# CV060_AI.net
KiCad netlist of a schematic drawn in Altium Designer
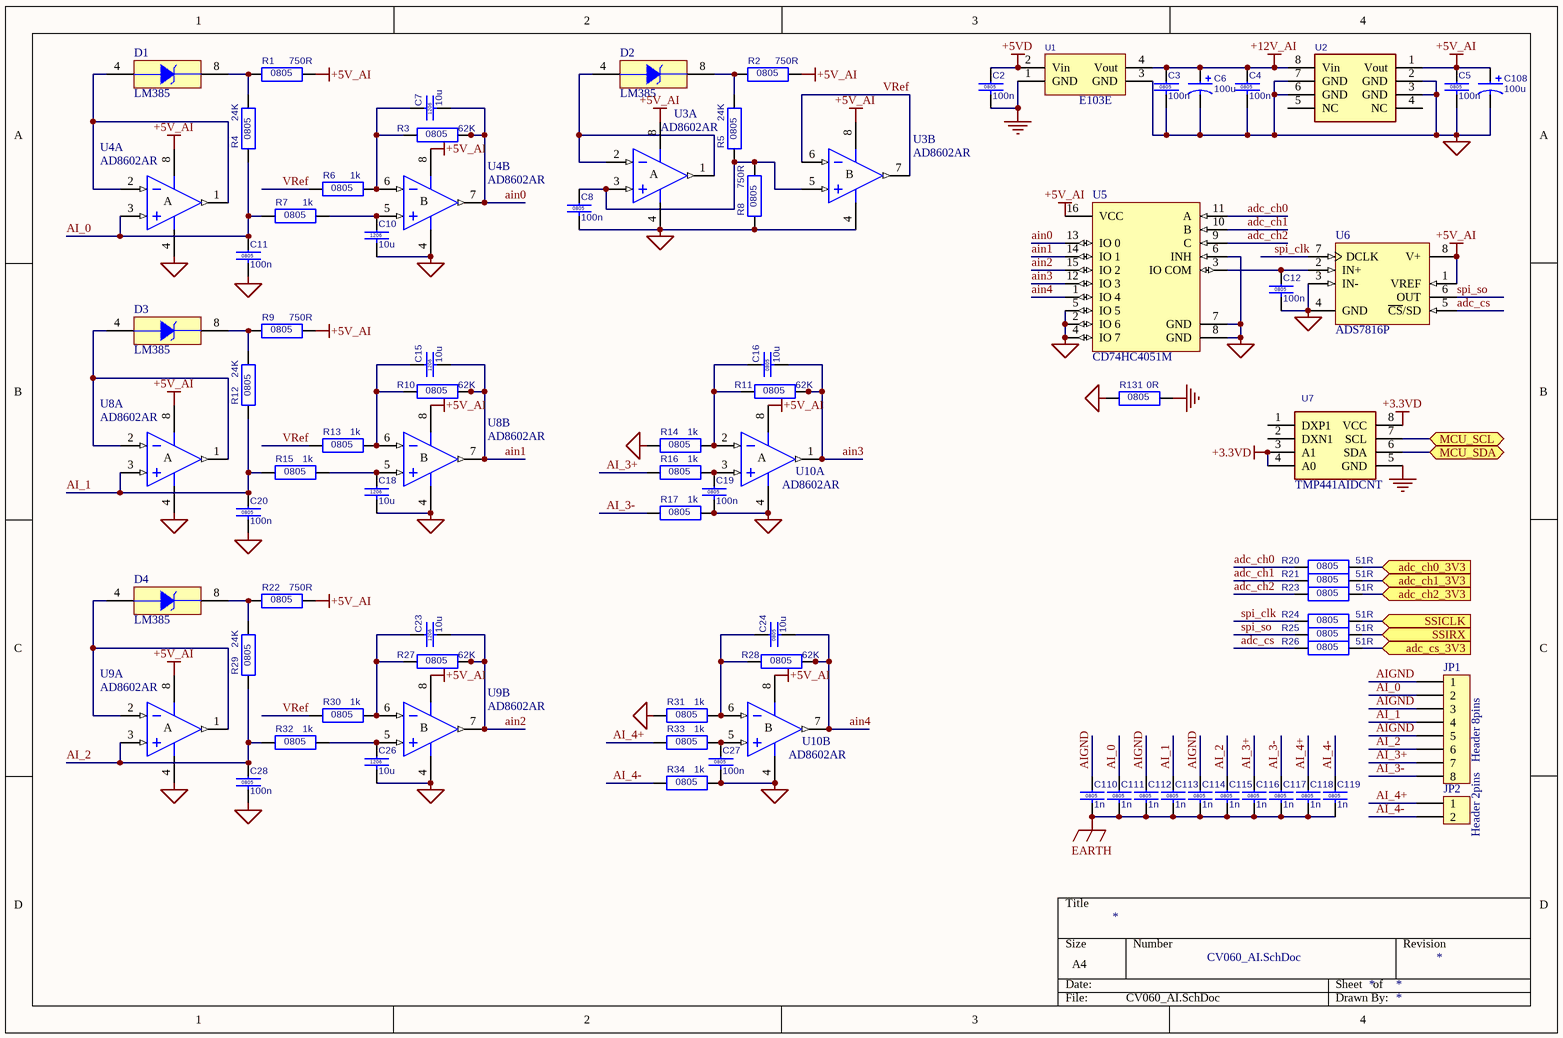
[diagram p0: CV060_AI.SchDoc]

(export (version "E")
  (design (tool "Eeschema 10.0.6"))
  (components
    (comp (ref "C2")
      (value "100n")
      (footprint "RC0805")
      (description "Chip capacitor, 20p")
      (fields
        (field (name "VOLTAGE") "50V")
        (field (name "MANUFACTURER") "KEMET, YAGEO")
        (field (name "CASE") "0805")
        (field (name "PUBLISHER") "ppavlov")
      )
      (libsource (lib "Aldiva_Altium_Library") (part "Capacitor_nonpolar_case"))
    )
    (comp (ref "C3")
      (value "100n")
      (footprint "RC0805")
      (description "Chip capacitor, 20p")
      (fields
        (field (name "VOLTAGE") "50V")
        (field (name "MANUFACTURER") "KEMET, YAGEO")
        (field (name "CASE") "0805")
        (field (name "PUBLISHER") "ppavlov")
      )
      (libsource (lib "Aldiva_Altium_Library") (part "Capacitor_nonpolar_case"))
    )
    (comp (ref "C4")
      (value "100n")
      (footprint "RC0805")
      (description "Chip capacitor, 20p")
      (fields
        (field (name "VOLTAGE") "50V")
        (field (name "MANUFACTURER") "KEMET, YAGEO")
        (field (name "CASE") "0805")
        (field (name "PUBLISHER") "ppavlov")
      )
      (libsource (lib "Aldiva_Altium_Library") (part "Capacitor_nonpolar_case"))
    )
    (comp (ref "C5")
      (value "100n")
      (footprint "RC0805")
      (description "Chip capacitor, 20p")
      (fields
        (field (name "VOLTAGE") "50V")
        (field (name "MANUFACTURER") "KEMET, YAGEO")
        (field (name "CASE") "0805")
        (field (name "PUBLISHER") "ppavlov")
      )
      (libsource (lib "Aldiva_Altium_Library") (part "Capacitor_nonpolar_case"))
    )
    (comp (ref "C6")
      (value "100u")
      (footprint "CEH12.5D5P2.5")
      (description "Electrolytic capacitor")
      (fields
        (field (name "PART NUMBER") "CEH12.5D5P2.5M-16V-100U")
        (field (name "VOLTAGE") "16V")
        (field (name "PUBLISHER") "ppavlov")
      )
      (libsource (lib "Aldiva_Altium_Library") (part "Capacitor_polar"))
    )
    (comp (ref "C7")
      (value "10u")
      (footprint "RC1206")
      (description "Chip capacitor, 20p")
      (fields
        (field (name "VOLTAGE") "10V")
        (field (name "MANUFACTURER") "AVX")
        (field (name "CASE") "1206")
        (field (name "PUBLISHER") "tkondratyuk")
      )
      (libsource (lib "Aldiva_Altium_Library") (part "Capacitor_nonpolar_case"))
    )
    (comp (ref "C8")
      (value "100n")
      (footprint "RC0805")
      (description "Chip capacitor, 20p")
      (fields
        (field (name "VOLTAGE") "50V")
        (field (name "MANUFACTURER") "KEMET, YAGEO")
        (field (name "CASE") "0805")
        (field (name "PUBLISHER") "ppavlov")
      )
      (libsource (lib "Aldiva_Altium_Library") (part "Capacitor_nonpolar_case"))
    )
    (comp (ref "C10")
      (value "10u")
      (footprint "RC1206")
      (description "Chip capacitor, 20p")
      (fields
        (field (name "VOLTAGE") "10V")
        (field (name "MANUFACTURER") "AVX")
        (field (name "CASE") "1206")
        (field (name "PUBLISHER") "tkondratyuk")
      )
      (libsource (lib "Aldiva_Altium_Library") (part "Capacitor_nonpolar_case"))
    )
    (comp (ref "C11")
      (value "100n")
      (footprint "RC0805")
      (description "Chip capacitor, 20p")
      (fields
        (field (name "VOLTAGE") "50V")
        (field (name "MANUFACTURER") "KEMET, YAGEO")
        (field (name "CASE") "0805")
        (field (name "PUBLISHER") "ppavlov")
      )
      (libsource (lib "Aldiva_Altium_Library") (part "Capacitor_nonpolar_case"))
    )
    (comp (ref "C12")
      (value "100n")
      (footprint "RC0805")
      (description "Chip capacitor, 20p")
      (fields
        (field (name "VOLTAGE") "50V")
        (field (name "MANUFACTURER") "KEMET, YAGEO")
        (field (name "CASE") "0805")
        (field (name "PUBLISHER") "ppavlov")
      )
      (libsource (lib "Aldiva_Altium_Library") (part "Capacitor_nonpolar_case"))
    )
    (comp (ref "C15")
      (value "10u")
      (footprint "RC1206")
      (description "Chip capacitor, 20p")
      (fields
        (field (name "VOLTAGE") "10V")
        (field (name "MANUFACTURER") "AVX")
        (field (name "CASE") "1206")
        (field (name "PUBLISHER") "tkondratyuk")
      )
      (libsource (lib "Aldiva_Altium_Library") (part "Capacitor_nonpolar_case"))
    )
    (comp (ref "C16")
      (value "10u")
      (footprint "RC0805")
      (description "Chip capacitor, 20p")
      (fields
        (field (name "VOLTAGE") "16V")
        (field (name "MANUFACTURER") "KEMET, YAGEO")
        (field (name "CASE") "0805")
        (field (name "PUBLISHER") "tkondratyuk")
      )
      (libsource (lib "Aldiva_Altium_Library") (part "Capacitor_nonpolar_case"))
    )
    (comp (ref "C18")
      (value "10u")
      (footprint "RC1206")
      (description "Chip capacitor, 20p")
      (fields
        (field (name "VOLTAGE") "10V")
        (field (name "MANUFACTURER") "AVX")
        (field (name "CASE") "1206")
        (field (name "PUBLISHER") "tkondratyuk")
      )
      (libsource (lib "Aldiva_Altium_Library") (part "Capacitor_nonpolar_case"))
    )
    (comp (ref "C19")
      (value "100n")
      (footprint "RC0805")
      (description "Chip capacitor, 20p")
      (fields
        (field (name "VOLTAGE") "50V")
        (field (name "MANUFACTURER") "KEMET, YAGEO")
        (field (name "CASE") "0805")
        (field (name "PUBLISHER") "ppavlov")
      )
      (libsource (lib "Aldiva_Altium_Library") (part "Capacitor_nonpolar_case"))
    )
    (comp (ref "C20")
      (value "100n")
      (footprint "RC0805")
      (description "Chip capacitor, 20p")
      (fields
        (field (name "VOLTAGE") "50V")
        (field (name "MANUFACTURER") "KEMET, YAGEO")
        (field (name "CASE") "0805")
        (field (name "PUBLISHER") "ppavlov")
      )
      (libsource (lib "Aldiva_Altium_Library") (part "Capacitor_nonpolar_case"))
    )
    (comp (ref "C23")
      (value "10u")
      (footprint "RC1206")
      (description "Chip capacitor, 20p")
      (fields
        (field (name "VOLTAGE") "10V")
        (field (name "MANUFACTURER") "AVX")
        (field (name "CASE") "1206")
        (field (name "PUBLISHER") "tkondratyuk")
      )
      (libsource (lib "Aldiva_Altium_Library") (part "Capacitor_nonpolar_case"))
    )
    (comp (ref "C24")
      (value "10u")
      (footprint "RC0805")
      (description "Chip capacitor, 20p")
      (fields
        (field (name "VOLTAGE") "16V")
        (field (name "MANUFACTURER") "KEMET, YAGEO")
        (field (name "CASE") "0805")
        (field (name "PUBLISHER") "tkondratyuk")
      )
      (libsource (lib "Aldiva_Altium_Library") (part "Capacitor_nonpolar_case"))
    )
    (comp (ref "C26")
      (value "10u")
      (footprint "RC1206")
      (description "Chip capacitor, 20p")
      (fields
        (field (name "VOLTAGE") "10V")
        (field (name "MANUFACTURER") "AVX")
        (field (name "CASE") "1206")
        (field (name "PUBLISHER") "tkondratyuk")
      )
      (libsource (lib "Aldiva_Altium_Library") (part "Capacitor_nonpolar_case"))
    )
    (comp (ref "C27")
      (value "100n")
      (footprint "RC0805")
      (description "Chip capacitor, 20p")
      (fields
        (field (name "VOLTAGE") "50V")
        (field (name "MANUFACTURER") "KEMET, YAGEO")
        (field (name "CASE") "0805")
        (field (name "PUBLISHER") "ppavlov")
      )
      (libsource (lib "Aldiva_Altium_Library") (part "Capacitor_nonpolar_case"))
    )
    (comp (ref "C28")
      (value "100n")
      (footprint "RC0805")
      (description "Chip capacitor, 20p")
      (fields
        (field (name "VOLTAGE") "50V")
        (field (name "MANUFACTURER") "KEMET, YAGEO")
        (field (name "CASE") "0805")
        (field (name "PUBLISHER") "ppavlov")
      )
      (libsource (lib "Aldiva_Altium_Library") (part "Capacitor_nonpolar_case"))
    )
    (comp (ref "C108")
      (value "100u")
      (footprint "CEH12.5D5P2.5")
      (description "Electrolytic capacitor")
      (fields
        (field (name "PART NUMBER") "CEH12.5D5P2.5M-16V-100U")
        (field (name "VOLTAGE") "16V")
        (field (name "PUBLISHER") "ppavlov")
      )
      (libsource (lib "Aldiva_Altium_Library") (part "Capacitor_polar"))
    )
    (comp (ref "C110")
      (value "1n")
      (footprint "RC0805")
      (description "Chip capacitor, 20p")
      (fields
        (field (name "VOLTAGE") "50V")
        (field (name "MANUFACTURER") "KEMET, YAGEO")
        (field (name "CASE") "0805")
        (field (name "PUBLISHER") "ppavlov")
      )
      (libsource (lib "Aldiva_Altium_Library") (part "Capacitor_nonpolar_case"))
    )
    (comp (ref "C111")
      (value "1n")
      (footprint "RC0805")
      (description "Chip capacitor, 20p")
      (fields
        (field (name "VOLTAGE") "50V")
        (field (name "MANUFACTURER") "KEMET, YAGEO")
        (field (name "CASE") "0805")
        (field (name "PUBLISHER") "ppavlov")
      )
      (libsource (lib "Aldiva_Altium_Library") (part "Capacitor_nonpolar_case"))
    )
    (comp (ref "C112")
      (value "1n")
      (footprint "RC0805")
      (description "Chip capacitor, 20p")
      (fields
        (field (name "VOLTAGE") "50V")
        (field (name "MANUFACTURER") "KEMET, YAGEO")
        (field (name "CASE") "0805")
        (field (name "PUBLISHER") "ppavlov")
      )
      (libsource (lib "Aldiva_Altium_Library") (part "Capacitor_nonpolar_case"))
    )
    (comp (ref "C113")
      (value "1n")
      (footprint "RC0805")
      (description "Chip capacitor, 20p")
      (fields
        (field (name "VOLTAGE") "50V")
        (field (name "MANUFACTURER") "KEMET, YAGEO")
        (field (name "CASE") "0805")
        (field (name "PUBLISHER") "ppavlov")
      )
      (libsource (lib "Aldiva_Altium_Library") (part "Capacitor_nonpolar_case"))
    )
    (comp (ref "C114")
      (value "1n")
      (footprint "RC0805")
      (description "Chip capacitor, 20p")
      (fields
        (field (name "VOLTAGE") "50V")
        (field (name "MANUFACTURER") "KEMET, YAGEO")
        (field (name "CASE") "0805")
        (field (name "PUBLISHER") "ppavlov")
      )
      (libsource (lib "Aldiva_Altium_Library") (part "Capacitor_nonpolar_case"))
    )
    (comp (ref "C115")
      (value "1n")
      (footprint "RC0805")
      (description "Chip capacitor, 20p")
      (fields
        (field (name "VOLTAGE") "50V")
        (field (name "MANUFACTURER") "KEMET, YAGEO")
        (field (name "CASE") "0805")
        (field (name "PUBLISHER") "ppavlov")
      )
      (libsource (lib "Aldiva_Altium_Library") (part "Capacitor_nonpolar_case"))
    )
    (comp (ref "C116")
      (value "1n")
      (footprint "RC0805")
      (description "Chip capacitor, 20p")
      (fields
        (field (name "VOLTAGE") "50V")
        (field (name "MANUFACTURER") "KEMET, YAGEO")
        (field (name "CASE") "0805")
        (field (name "PUBLISHER") "ppavlov")
      )
      (libsource (lib "Aldiva_Altium_Library") (part "Capacitor_nonpolar_case"))
    )
    (comp (ref "C117")
      (value "1n")
      (footprint "RC0805")
      (description "Chip capacitor, 20p")
      (fields
        (field (name "VOLTAGE") "50V")
        (field (name "MANUFACTURER") "KEMET, YAGEO")
        (field (name "CASE") "0805")
        (field (name "PUBLISHER") "ppavlov")
      )
      (libsource (lib "Aldiva_Altium_Library") (part "Capacitor_nonpolar_case"))
    )
    (comp (ref "C118")
      (value "1n")
      (footprint "RC0805")
      (description "Chip capacitor, 20p")
      (fields
        (field (name "VOLTAGE") "50V")
        (field (name "MANUFACTURER") "KEMET, YAGEO")
        (field (name "CASE") "0805")
        (field (name "PUBLISHER") "ppavlov")
      )
      (libsource (lib "Aldiva_Altium_Library") (part "Capacitor_nonpolar_case"))
    )
    (comp (ref "C119")
      (value "1n")
      (footprint "RC0805")
      (description "Chip capacitor, 20p")
      (fields
        (field (name "VOLTAGE") "50V")
        (field (name "MANUFACTURER") "KEMET, YAGEO")
        (field (name "CASE") "0805")
        (field (name "PUBLISHER") "ppavlov")
      )
      (libsource (lib "Aldiva_Altium_Library") (part "Capacitor_nonpolar_case"))
    )
    (comp (ref "D1")
      (value "LM385")
      (footprint "SO-8")
      (description "Micropower Voltage Reference Diode")
      (fields
        (field (name "PART NUMBER") "LM385BD-2-5")
        (field (name "MANUFACTURER") "TI")
        (field (name "PUBLISHER") "ppavlov")
      )
      (libsource (lib "Aldiva_Altium_Library") (part "LM385"))
    )
    (comp (ref "D2")
      (value "LM385")
      (footprint "SO-8")
      (description "Micropower Voltage Reference Diode")
      (fields
        (field (name "PART NUMBER") "LM385BD-2-5")
        (field (name "MANUFACTURER") "TI")
        (field (name "PUBLISHER") "ppavlov")
      )
      (libsource (lib "Aldiva_Altium_Library") (part "LM385"))
    )
    (comp (ref "D3")
      (value "LM385")
      (footprint "SO-8")
      (description "Micropower Voltage Reference Diode")
      (fields
        (field (name "PART NUMBER") "LM385BD-2-5")
        (field (name "MANUFACTURER") "TI")
        (field (name "PUBLISHER") "ppavlov")
      )
      (libsource (lib "Aldiva_Altium_Library") (part "LM385"))
    )
    (comp (ref "D4")
      (value "LM385")
      (footprint "SO-8")
      (description "Micropower Voltage Reference Diode")
      (fields
        (field (name "PART NUMBER") "LM385BD-2-5")
        (field (name "MANUFACTURER") "TI")
        (field (name "PUBLISHER") "ppavlov")
      )
      (libsource (lib "Aldiva_Altium_Library") (part "LM385"))
    )
    (comp (ref "JP1")
      (value "Header 8pins")
      (footprint "PHOENIX_5.08_8PINS")
      (description "5.08mm angled 8pins receptabe")
      (fields
        (field (name "PART NUMBER") "2EDGR-5.08-08P-14")
        (field (name "MANUFACTURER PART NUMBER") "2EDGR-5.0-08P-14")
        (field (name "PUBLISHER") "ppavlov")
      )
      (libsource (lib "Aldiva_Altium_Library") (part "Header 8pins"))
    )
    (comp (ref "JP2")
      (value "Header 2pins")
      (footprint "PHOENIX_5.08_2PINS")
      (description "5mm angled 2pins receptabe")
      (fields
        (field (name "PART NUMBER") "2EDGR-5.08-02P-14")
        (field (name "MANUFACTURER PART NUMBER") "2EDGR-5.0-02P-14")
        (field (name "PUBLISHER") "ppavlov")
      )
      (libsource (lib "Aldiva_Altium_Library") (part "Header 2pins"))
    )
    (comp (ref "R1")
      (value "750R")
      (footprint "RC0805")
      (description "Chip resistor")
      (fields
        (field (name "CASE") "0805")
        (field (name "PART NUMBER") "RC0805F-750R")
        (field (name "VOLTAGE") "200V")
        (field (name "PUBLISHER") "ppavlov")
      )
      (libsource (lib "Aldiva_Altium_Library") (part "Resistor"))
    )
    (comp (ref "R2")
      (value "750R")
      (footprint "RC0805")
      (description "Chip resistor")
      (fields
        (field (name "CASE") "0805")
        (field (name "PART NUMBER") "RC0805F-750R")
        (field (name "VOLTAGE") "200V")
        (field (name "PUBLISHER") "ppavlov")
      )
      (libsource (lib "Aldiva_Altium_Library") (part "Resistor"))
    )
    (comp (ref "R3")
      (value "62K")
      (footprint "RC0805")
      (description "Chip resistor")
      (fields
        (field (name "CASE") "0805")
        (field (name "PART NUMBER") "RC0805F-62K0")
        (field (name "VOLTAGE") "200V")
        (field (name "PUBLISHER") "ppavlov")
      )
      (libsource (lib "Aldiva_Altium_Library") (part "Resistor"))
    )
    (comp (ref "R4")
      (value "24K")
      (footprint "RC0805")
      (description "Chip resistor")
      (fields
        (field (name "CASE") "0805")
        (field (name "PART NUMBER") "RC0805F-24K0")
        (field (name "VOLTAGE") "200V")
        (field (name "PUBLISHER") "ppavlov")
      )
      (libsource (lib "Aldiva_Altium_Library") (part "Resistor"))
    )
    (comp (ref "R5")
      (value "24K")
      (footprint "RC0805")
      (description "Chip resistor")
      (fields
        (field (name "CASE") "0805")
        (field (name "PART NUMBER") "RC0805F-24K0")
        (field (name "VOLTAGE") "200V")
        (field (name "PUBLISHER") "ppavlov")
      )
      (libsource (lib "Aldiva_Altium_Library") (part "Resistor"))
    )
    (comp (ref "R6")
      (value "1k")
      (footprint "RC0805")
      (description "Chip resistor")
      (fields
        (field (name "CASE") "0805")
        (field (name "PART NUMBER") "RC0805F-1K00")
        (field (name "VOLTAGE") "200V")
        (field (name "PUBLISHER") "ppavlov")
      )
      (libsource (lib "Aldiva_Altium_Library") (part "Resistor"))
    )
    (comp (ref "R7")
      (value "1k")
      (footprint "RC0805")
      (description "Chip resistor")
      (fields
        (field (name "CASE") "0805")
        (field (name "PART NUMBER") "RC0805F-1K00")
        (field (name "VOLTAGE") "200V")
        (field (name "PUBLISHER") "ppavlov")
      )
      (libsource (lib "Aldiva_Altium_Library") (part "Resistor"))
    )
    (comp (ref "R8")
      (value "750R")
      (footprint "RC0805")
      (description "Chip resistor")
      (fields
        (field (name "CASE") "0805")
        (field (name "PART NUMBER") "RC0805F-750R")
        (field (name "VOLTAGE") "200V")
        (field (name "PUBLISHER") "ppavlov")
      )
      (libsource (lib "Aldiva_Altium_Library") (part "Resistor"))
    )
    (comp (ref "R9")
      (value "750R")
      (footprint "RC0805")
      (description "Chip resistor")
      (fields
        (field (name "CASE") "0805")
        (field (name "PART NUMBER") "RC0805F-750R")
        (field (name "VOLTAGE") "200V")
        (field (name "PUBLISHER") "ppavlov")
      )
      (libsource (lib "Aldiva_Altium_Library") (part "Resistor"))
    )
    (comp (ref "R10")
      (value "62K")
      (footprint "RC0805")
      (description "Chip resistor")
      (fields
        (field (name "CASE") "0805")
        (field (name "PART NUMBER") "RC0805F-62K0")
        (field (name "VOLTAGE") "200V")
        (field (name "PUBLISHER") "ppavlov")
      )
      (libsource (lib "Aldiva_Altium_Library") (part "Resistor"))
    )
    (comp (ref "R11")
      (value "62K")
      (footprint "RC0805")
      (description "Chip resistor")
      (fields
        (field (name "CASE") "0805")
        (field (name "PART NUMBER") "RC0805F-62K0")
        (field (name "VOLTAGE") "200V")
        (field (name "PUBLISHER") "ppavlov")
      )
      (libsource (lib "Aldiva_Altium_Library") (part "Resistor"))
    )
    (comp (ref "R12")
      (value "24K")
      (footprint "RC0805")
      (description "Chip resistor")
      (fields
        (field (name "CASE") "0805")
        (field (name "PART NUMBER") "RC0805F-24K0")
        (field (name "VOLTAGE") "200V")
        (field (name "PUBLISHER") "ppavlov")
      )
      (libsource (lib "Aldiva_Altium_Library") (part "Resistor"))
    )
    (comp (ref "R13")
      (value "1k")
      (footprint "RC0805")
      (description "Chip resistor")
      (fields
        (field (name "CASE") "0805")
        (field (name "PART NUMBER") "RC0805F-1K00")
        (field (name "VOLTAGE") "200V")
        (field (name "PUBLISHER") "ppavlov")
      )
      (libsource (lib "Aldiva_Altium_Library") (part "Resistor"))
    )
    (comp (ref "R14")
      (value "1k")
      (footprint "RC0805")
      (description "Chip resistor")
      (fields
        (field (name "CASE") "0805")
        (field (name "PART NUMBER") "RC0805F-1K00")
        (field (name "VOLTAGE") "200V")
        (field (name "PUBLISHER") "ppavlov")
      )
      (libsource (lib "Aldiva_Altium_Library") (part "Resistor"))
    )
    (comp (ref "R15")
      (value "1k")
      (footprint "RC0805")
      (description "Chip resistor")
      (fields
        (field (name "CASE") "0805")
        (field (name "PART NUMBER") "RC0805F-1K00")
        (field (name "VOLTAGE") "200V")
        (field (name "PUBLISHER") "ppavlov")
      )
      (libsource (lib "Aldiva_Altium_Library") (part "Resistor"))
    )
    (comp (ref "R16")
      (value "1k")
      (footprint "RC0805")
      (description "Chip resistor")
      (fields
        (field (name "CASE") "0805")
        (field (name "PART NUMBER") "RC0805F-1K00")
        (field (name "VOLTAGE") "200V")
        (field (name "PUBLISHER") "ppavlov")
      )
      (libsource (lib "Aldiva_Altium_Library") (part "Resistor"))
    )
    (comp (ref "R17")
      (value "1k")
      (footprint "RC0805")
      (description "Chip resistor")
      (fields
        (field (name "CASE") "0805")
        (field (name "PART NUMBER") "RC0805F-1K00")
        (field (name "VOLTAGE") "200V")
        (field (name "PUBLISHER") "ppavlov")
      )
      (libsource (lib "Aldiva_Altium_Library") (part "Resistor"))
    )
    (comp (ref "R20")
      (value "51R")
      (footprint "RC0805")
      (description "Chip resistor")
      (fields
        (field (name "CASE") "0805")
        (field (name "PART NUMBER") "RC0805F-51R0")
        (field (name "VOLTAGE") "200V")
        (field (name "PUBLISHER") "ppavlov")
      )
      (libsource (lib "Aldiva_Altium_Library") (part "Resistor"))
    )
    (comp (ref "R21")
      (value "51R")
      (footprint "RC0805")
      (description "Chip resistor")
      (fields
        (field (name "CASE") "0805")
        (field (name "PART NUMBER") "RC0805F-51R0")
        (field (name "VOLTAGE") "200V")
        (field (name "PUBLISHER") "ppavlov")
      )
      (libsource (lib "Aldiva_Altium_Library") (part "Resistor"))
    )
    (comp (ref "R22")
      (value "750R")
      (footprint "RC0805")
      (description "Chip resistor")
      (fields
        (field (name "CASE") "0805")
        (field (name "PART NUMBER") "RC0805F-750R")
        (field (name "VOLTAGE") "200V")
        (field (name "PUBLISHER") "ppavlov")
      )
      (libsource (lib "Aldiva_Altium_Library") (part "Resistor"))
    )
    (comp (ref "R23")
      (value "51R")
      (footprint "RC0805")
      (description "Chip resistor")
      (fields
        (field (name "CASE") "0805")
        (field (name "PART NUMBER") "RC0805F-51R0")
        (field (name "VOLTAGE") "200V")
        (field (name "PUBLISHER") "ppavlov")
      )
      (libsource (lib "Aldiva_Altium_Library") (part "Resistor"))
    )
    (comp (ref "R24")
      (value "51R")
      (footprint "RC0805")
      (description "Chip resistor")
      (fields
        (field (name "CASE") "0805")
        (field (name "PART NUMBER") "RC0805F-51R0")
        (field (name "VOLTAGE") "200V")
        (field (name "PUBLISHER") "ppavlov")
      )
      (libsource (lib "Aldiva_Altium_Library") (part "Resistor"))
    )
    (comp (ref "R25")
      (value "51R")
      (footprint "RC0805")
      (description "Chip resistor")
      (fields
        (field (name "CASE") "0805")
        (field (name "PART NUMBER") "RC0805F-51R0")
        (field (name "VOLTAGE") "200V")
        (field (name "PUBLISHER") "ppavlov")
      )
      (libsource (lib "Aldiva_Altium_Library") (part "Resistor"))
    )
    (comp (ref "R26")
      (value "51R")
      (footprint "RC0805")
      (description "Chip resistor")
      (fields
        (field (name "CASE") "0805")
        (field (name "PART NUMBER") "RC0805F-51R0")
        (field (name "VOLTAGE") "200V")
        (field (name "PUBLISHER") "ppavlov")
      )
      (libsource (lib "Aldiva_Altium_Library") (part "Resistor"))
    )
    (comp (ref "R27")
      (value "62K")
      (footprint "RC0805")
      (description "Chip resistor")
      (fields
        (field (name "CASE") "0805")
        (field (name "PART NUMBER") "RC0805F-62K0")
        (field (name "VOLTAGE") "200V")
        (field (name "PUBLISHER") "ppavlov")
      )
      (libsource (lib "Aldiva_Altium_Library") (part "Resistor"))
    )
    (comp (ref "R28")
      (value "62K")
      (footprint "RC0805")
      (description "Chip resistor")
      (fields
        (field (name "CASE") "0805")
        (field (name "PART NUMBER") "RC0805F-62K0")
        (field (name "VOLTAGE") "200V")
        (field (name "PUBLISHER") "ppavlov")
      )
      (libsource (lib "Aldiva_Altium_Library") (part "Resistor"))
    )
    (comp (ref "R29")
      (value "24K")
      (footprint "RC0805")
      (description "Chip resistor")
      (fields
        (field (name "CASE") "0805")
        (field (name "PART NUMBER") "RC0805F-24K0")
        (field (name "VOLTAGE") "200V")
        (field (name "PUBLISHER") "ppavlov")
      )
      (libsource (lib "Aldiva_Altium_Library") (part "Resistor"))
    )
    (comp (ref "R30")
      (value "1k")
      (footprint "RC0805")
      (description "Chip resistor")
      (fields
        (field (name "CASE") "0805")
        (field (name "PART NUMBER") "RC0805F-1K00")
        (field (name "VOLTAGE") "200V")
        (field (name "PUBLISHER") "ppavlov")
      )
      (libsource (lib "Aldiva_Altium_Library") (part "Resistor"))
    )
    (comp (ref "R31")
      (value "1k")
      (footprint "RC0805")
      (description "Chip resistor")
      (fields
        (field (name "CASE") "0805")
        (field (name "PART NUMBER") "RC0805F-1K00")
        (field (name "VOLTAGE") "200V")
        (field (name "PUBLISHER") "ppavlov")
      )
      (libsource (lib "Aldiva_Altium_Library") (part "Resistor"))
    )
    (comp (ref "R32")
      (value "1k")
      (footprint "RC0805")
      (description "Chip resistor")
      (fields
        (field (name "CASE") "0805")
        (field (name "PART NUMBER") "RC0805F-1K00")
        (field (name "VOLTAGE") "200V")
        (field (name "PUBLISHER") "ppavlov")
      )
      (libsource (lib "Aldiva_Altium_Library") (part "Resistor"))
    )
    (comp (ref "R33")
      (value "1k")
      (footprint "RC0805")
      (description "Chip resistor")
      (fields
        (field (name "CASE") "0805")
        (field (name "PART NUMBER") "RC0805F-1K00")
        (field (name "VOLTAGE") "200V")
        (field (name "PUBLISHER") "ppavlov")
      )
      (libsource (lib "Aldiva_Altium_Library") (part "Resistor"))
    )
    (comp (ref "R34")
      (value "1k")
      (footprint "RC0805")
      (description "Chip resistor")
      (fields
        (field (name "CASE") "0805")
        (field (name "PART NUMBER") "RC0805F-1K00")
        (field (name "VOLTAGE") "200V")
        (field (name "PUBLISHER") "ppavlov")
      )
      (libsource (lib "Aldiva_Altium_Library") (part "Resistor"))
    )
    (comp (ref "R131")
      (value "0R")
      (footprint "RC0805")
      (description "Chip resistor")
      (fields
        (field (name "CASE") "0805")
        (field (name "PART NUMBER") "RC0805F-000R")
        (field (name "VOLTAGE") "200V")
        (field (name "PUBLISHER") "ppavlov")
      )
      (libsource (lib "Aldiva_Altium_Library") (part "Resistor"))
    )
    (comp (ref "U1")
      (value "~")
      (footprint "SIP4")
      (description "1W Insulated DCDC converter 5 to 12V")
      (fields
        (field (name "PART NUMBER") "1-05-12S")
        (field (name "MANUFACTURER") "TI")
        (field (name "MANUFACTURER PART NUMBER") "E103E")
        (field (name "PUBLISHER") "ppavlov")
      )
      (libsource (lib "Aldiva_Altium_Library") (part "DCDC"))
    )
    (comp (ref "U2")
      (value "L78L05CD")
      (footprint "SO-8")
      (description "Regulator 100ma 5V")
      (fields (field (name "MANUFACTURER") "ST") (field (name "PUBLISHER") "ppavlov"))
      (libsource (lib "Aldiva_Altium_Library") (part "78L05"))
    )
    (comp (ref "U3")
      (value "AD8602AR")
      (footprint "SO-8")
      (description "Dual Precision, Low-Power BiFET Operational Amplifier")
      (fields (field (name "MANUFACTURER") "AD") (field (name "PUBLISHER") "ppavlov"))
      (libsource (lib "Aldiva_Altium_Library") (part "AD8602AR"))
    )
    (comp (ref "U4")
      (value "AD8602AR")
      (footprint "SO-8")
      (description "Dual Precision, Low-Power BiFET Operational Amplifier")
      (fields (field (name "MANUFACTURER") "AD") (field (name "PUBLISHER") "ppavlov"))
      (libsource (lib "Aldiva_Altium_Library") (part "AD8602AR"))
    )
    (comp (ref "U5")
      (value "CD74HC4051M")
      (footprint "SO-16")
      (description "High-Speed CMOS Logic\r\nAnalog Multiplexers/Demultiplexers")
      (fields (field (name "MANUFACTURER") "TI") (field (name "PUBLISHER") "ppavlov"))
      (libsource (lib "Aldiva_Altium_Library") (part "CD74HC4051M"))
    )
    (comp (ref "U6")
      (value "ADS7816P")
      (footprint "DIP-8")
      (description "12bit ADC")
      (fields (field (name "MANUFACTURER") "TI") (field (name "PUBLISHER") "ppavlov"))
      (libsource (lib "Aldiva_Altium_Library") (part "ADS7816P"))
    )
    (comp (ref "U7")
      (value "TMP441AIDCNT")
      (footprint "SOT23-8")
      (description "± 1 ° C TEMPERATURE SENSOR\r\nwith Automatic Beta Compensation")
      (fields (field (name "MANUFACTURER") "TI") (field (name "PUBLISHER") "ppavlov"))
      (libsource (lib "Aldiva_Altium_Library") (part "TMP441"))
    )
    (comp (ref "U8")
      (value "AD8602AR")
      (footprint "SO-8")
      (description "Dual Precision, Low-Power BiFET Operational Amplifier")
      (fields (field (name "MANUFACTURER") "AD") (field (name "PUBLISHER") "ppavlov"))
      (libsource (lib "Aldiva_Altium_Library") (part "AD8602AR"))
    )
    (comp (ref "U9")
      (value "AD8602AR")
      (footprint "SO-8")
      (description "Dual Precision, Low-Power BiFET Operational Amplifier")
      (fields (field (name "MANUFACTURER") "AD") (field (name "PUBLISHER") "ppavlov"))
      (libsource (lib "Aldiva_Altium_Library") (part "AD8602AR"))
    )
    (comp (ref "U10")
      (value "AD8602AR")
      (footprint "SO-8")
      (description "Dual Precision, Low-Power BiFET Operational Amplifier")
      (fields (field (name "MANUFACTURER") "AD") (field (name "PUBLISHER") "ppavlov"))
      (libsource (lib "Aldiva_Altium_Library") (part "AD8602AR"))
    )
  )
  (nets
    (net (code "1") (name "+3.3VD") (class "Default")
      (node (ref "U7") (pin "3") (pinfunction "A1_3") (pintype "passive"))
      (node (ref "U7") (pin "4") (pinfunction "A0_4") (pintype "passive"))
      (node (ref "U7") (pin "8") (pinfunction "VCC_8") (pintype "passive"))
    )
    (net (code "2") (name "+5VD") (class "Default")
      (node (ref "C2") (pin "1") (pinfunction "1_1") (pintype "passive"))
      (node (ref "U1") (pin "2") (pinfunction "Vin_2") (pintype "passive"))
    )
    (net (code "3") (name "+5V_AI") (class "Default")
      (node (ref "C108") (pin "1") (pinfunction "1_1") (pintype "passive"))
      (node (ref "C5") (pin "1") (pinfunction "1_1") (pintype "passive"))
      (node (ref "R1") (pin "2") (pinfunction "2_2") (pintype "passive"))
      (node (ref "R2") (pin "2") (pinfunction "2_2") (pintype "passive"))
      (node (ref "R22") (pin "2") (pinfunction "2_2") (pintype "passive"))
      (node (ref "R9") (pin "2") (pinfunction "2_2") (pintype "passive"))
      (node (ref "U10") (pin "8") (pinfunction "V+_8") (pintype "power_in"))
      (node (ref "U2") (pin "1") (pinfunction "Vout_1") (pintype "passive"))
      (node (ref "U3") (pin "8") (pinfunction "V+_8") (pintype "power_in"))
      (node (ref "U4") (pin "8") (pinfunction "V+_8") (pintype "power_in"))
      (node (ref "U5") (pin "16") (pinfunction "VCC_16") (pintype "power_in"))
      (node (ref "U6") (pin "1") (pinfunction "VREF_1") (pintype "input"))
      (node (ref "U6") (pin "8") (pinfunction "V+_8") (pintype "power_in"))
      (node (ref "U8") (pin "8") (pinfunction "V+_8") (pintype "power_in"))
      (node (ref "U9") (pin "8") (pinfunction "V+_8") (pintype "power_in"))
    )
    (net (code "4") (name "+12V_AI") (class "Default")
      (node (ref "C3") (pin "1") (pinfunction "1_1") (pintype "passive"))
      (node (ref "C4") (pin "1") (pinfunction "1_1") (pintype "passive"))
      (node (ref "C6") (pin "1") (pinfunction "1_1") (pintype "passive"))
      (node (ref "U1") (pin "4") (pinfunction "Vout_4") (pintype "passive"))
      (node (ref "U2") (pin "8") (pinfunction "Vin_8") (pintype "passive"))
    )
    (net (code "5") (name "/AI_0") (class "Default")
      (node (ref "C11") (pin "1") (pinfunction "1_1") (pintype "passive"))
      (node (ref "C111") (pin "1") (pinfunction "1_1") (pintype "passive"))
      (node (ref "JP1") (pin "2") (pinfunction "2_2") (pintype "passive"))
      (node (ref "R4") (pin "1") (pinfunction "1_1") (pintype "passive"))
      (node (ref "R7") (pin "1") (pinfunction "1_1") (pintype "passive"))
      (node (ref "U4") (pin "3") (pinfunction "IN+_3") (pintype "input"))
    )
    (net (code "6") (name "/AI_1") (class "Default")
      (node (ref "C113") (pin "1") (pinfunction "1_1") (pintype "passive"))
      (node (ref "C20") (pin "1") (pinfunction "1_1") (pintype "passive"))
      (node (ref "JP1") (pin "4") (pinfunction "4_4") (pintype "passive"))
      (node (ref "R12") (pin "1") (pinfunction "1_1") (pintype "passive"))
      (node (ref "R15") (pin "1") (pinfunction "1_1") (pintype "passive"))
      (node (ref "U8") (pin "3") (pinfunction "IN+_3") (pintype "input"))
    )
    (net (code "7") (name "/AI_2") (class "Default")
      (node (ref "C115") (pin "1") (pinfunction "1_1") (pintype "passive"))
      (node (ref "C28") (pin "1") (pinfunction "1_1") (pintype "passive"))
      (node (ref "JP1") (pin "6") (pinfunction "6_6") (pintype "passive"))
      (node (ref "R29") (pin "1") (pinfunction "1_1") (pintype "passive"))
      (node (ref "R32") (pin "1") (pinfunction "1_1") (pintype "passive"))
      (node (ref "U9") (pin "3") (pinfunction "IN+_3") (pintype "input"))
    )
    (net (code "8") (name "/AI_3+") (class "Default")
      (node (ref "C116") (pin "1") (pinfunction "1_1") (pintype "passive"))
      (node (ref "JP1") (pin "7") (pinfunction "7_7") (pintype "passive"))
      (node (ref "R16") (pin "1") (pinfunction "1_1") (pintype "passive"))
    )
    (net (code "9") (name "/AI_3-") (class "Default")
      (node (ref "C117") (pin "1") (pinfunction "1_1") (pintype "passive"))
      (node (ref "JP1") (pin "8") (pinfunction "8_8") (pintype "passive"))
      (node (ref "R17") (pin "1") (pinfunction "1_1") (pintype "passive"))
    )
    (net (code "10") (name "/AI_4+") (class "Default")
      (node (ref "C118") (pin "1") (pinfunction "1_1") (pintype "passive"))
      (node (ref "JP2") (pin "1") (pinfunction "1_1") (pintype "passive"))
      (node (ref "R33") (pin "1") (pinfunction "1_1") (pintype "passive"))
    )
    (net (code "11") (name "/AI_4-") (class "Default")
      (node (ref "C119") (pin "1") (pinfunction "1_1") (pintype "passive"))
      (node (ref "JP2") (pin "2") (pinfunction "2_2") (pintype "passive"))
      (node (ref "R34") (pin "1") (pinfunction "1_1") (pintype "passive"))
    )
    (net (code "12") (name "/MCU_SCL") (class "Default")
      (node (ref "U7") (pin "7") (pinfunction "SCL_7") (pintype "passive"))
    )
    (net (code "13") (name "/MCU_SDA") (class "Default")
      (node (ref "U7") (pin "6") (pinfunction "SDA_6") (pintype "passive"))
    )
    (net (code "14") (name "/SSICLK") (class "Default")
      (node (ref "R24") (pin "2") (pinfunction "2_2") (pintype "passive"))
    )
    (net (code "15") (name "/SSIRX") (class "Default")
      (node (ref "R25") (pin "2") (pinfunction "2_2") (pintype "passive"))
    )
    (net (code "16") (name "/VRef") (class "Default")
      (node (ref "R13") (pin "1") (pinfunction "1_1") (pintype "passive"))
      (node (ref "R30") (pin "1") (pinfunction "1_1") (pintype "passive"))
      (node (ref "R6") (pin "1") (pinfunction "1_1") (pintype "passive"))
      (node (ref "U3") (pin "6") (pinfunction "IN-_6") (pintype "input"))
      (node (ref "U3") (pin "7") (pinfunction "OUT_7") (pintype "output"))
    )
    (net (code "17") (name "/adc_ch0") (class "Default")
      (node (ref "R20") (pin "1") (pinfunction "1_1") (pintype "passive"))
      (node (ref "U5") (pin "11") (pinfunction "A_11") (pintype "input"))
    )
    (net (code "18") (name "/adc_ch0_3V3") (class "Default")
      (node (ref "R20") (pin "2") (pinfunction "2_2") (pintype "passive"))
    )
    (net (code "19") (name "/adc_ch1") (class "Default")
      (node (ref "R21") (pin "1") (pinfunction "1_1") (pintype "passive"))
      (node (ref "U5") (pin "10") (pinfunction "B_10") (pintype "input"))
    )
    (net (code "20") (name "/adc_ch1_3V3") (class "Default")
      (node (ref "R21") (pin "2") (pinfunction "2_2") (pintype "passive"))
    )
    (net (code "21") (name "/adc_ch2") (class "Default")
      (node (ref "R23") (pin "1") (pinfunction "1_1") (pintype "passive"))
      (node (ref "U5") (pin "9") (pinfunction "C_9") (pintype "input"))
    )
    (net (code "22") (name "/adc_ch2_3V3") (class "Default")
      (node (ref "R23") (pin "2") (pinfunction "2_2") (pintype "passive"))
    )
    (net (code "23") (name "/adc_cs") (class "Default")
      (node (ref "R26") (pin "1") (pinfunction "1_1") (pintype "passive"))
      (node (ref "U6") (pin "5") (pinfunction "~{CS}/SD_5") (pintype "input"))
    )
    (net (code "24") (name "/adc_cs_3V3") (class "Default")
      (node (ref "R26") (pin "2") (pinfunction "2_2") (pintype "passive"))
    )
    (net (code "25") (name "/ain0") (class "Default")
      (node (ref "C7") (pin "2") (pinfunction "2_2") (pintype "passive"))
      (node (ref "R3") (pin "2") (pinfunction "2_2") (pintype "passive"))
      (node (ref "U4") (pin "7") (pinfunction "OUT_7") (pintype "output"))
      (node (ref "U5") (pin "13") (pinfunction "IO_0_13") (pintype "bidirectional"))
    )
    (net (code "26") (name "/ain1") (class "Default")
      (node (ref "C15") (pin "2") (pinfunction "2_2") (pintype "passive"))
      (node (ref "R10") (pin "2") (pinfunction "2_2") (pintype "passive"))
      (node (ref "U5") (pin "14") (pinfunction "IO_1_14") (pintype "bidirectional"))
      (node (ref "U8") (pin "7") (pinfunction "OUT_7") (pintype "output"))
    )
    (net (code "27") (name "/ain2") (class "Default")
      (node (ref "C23") (pin "2") (pinfunction "2_2") (pintype "passive"))
      (node (ref "R27") (pin "2") (pinfunction "2_2") (pintype "passive"))
      (node (ref "U5") (pin "15") (pinfunction "IO_2_15") (pintype "bidirectional"))
      (node (ref "U9") (pin "7") (pinfunction "OUT_7") (pintype "output"))
    )
    (net (code "28") (name "/ain3") (class "Default")
      (node (ref "C16") (pin "2") (pinfunction "2_2") (pintype "passive"))
      (node (ref "R11") (pin "2") (pinfunction "2_2") (pintype "passive"))
      (node (ref "U10") (pin "1") (pinfunction "OUT_1") (pintype "output"))
      (node (ref "U5") (pin "12") (pinfunction "IO_3_12") (pintype "bidirectional"))
    )
    (net (code "29") (name "/ain4") (class "Default")
      (node (ref "C24") (pin "2") (pinfunction "2_2") (pintype "passive"))
      (node (ref "R28") (pin "2") (pinfunction "2_2") (pintype "passive"))
      (node (ref "U10") (pin "7") (pinfunction "OUT_7") (pintype "output"))
      (node (ref "U5") (pin "1") (pinfunction "IO_4_1") (pintype "bidirectional"))
    )
    (net (code "30") (name "/spi_clk") (class "Default")
      (node (ref "R24") (pin "1") (pinfunction "1_1") (pintype "passive"))
      (node (ref "U6") (pin "7") (pinfunction "DCLK_7") (pintype "input"))
    )
    (net (code "31") (name "/spi_so") (class "Default")
      (node (ref "R25") (pin "1") (pinfunction "1_1") (pintype "passive"))
      (node (ref "U6") (pin "6") (pinfunction "OUT_6") (pintype "tri_state"))
    )
    (net (code "32") (name "AIGND") (class "Default")
      (node (ref "C10") (pin "2") (pinfunction "2_2") (pintype "passive"))
      (node (ref "C108") (pin "2") (pinfunction "2_2") (pintype "passive"))
      (node (ref "C11") (pin "2") (pinfunction "2_2") (pintype "passive"))
      (node (ref "C110") (pin "1") (pinfunction "1_1") (pintype "passive"))
      (node (ref "C112") (pin "1") (pinfunction "1_1") (pintype "passive"))
      (node (ref "C114") (pin "1") (pinfunction "1_1") (pintype "passive"))
      (node (ref "C12") (pin "2") (pinfunction "2_2") (pintype "passive"))
      (node (ref "C18") (pin "2") (pinfunction "2_2") (pintype "passive"))
      (node (ref "C19") (pin "2") (pinfunction "2_2") (pintype "passive"))
      (node (ref "C20") (pin "2") (pinfunction "2_2") (pintype "passive"))
      (node (ref "C26") (pin "2") (pinfunction "2_2") (pintype "passive"))
      (node (ref "C27") (pin "2") (pinfunction "2_2") (pintype "passive"))
      (node (ref "C28") (pin "2") (pinfunction "2_2") (pintype "passive"))
      (node (ref "C3") (pin "2") (pinfunction "2_2") (pintype "passive"))
      (node (ref "C4") (pin "2") (pinfunction "2_2") (pintype "passive"))
      (node (ref "C5") (pin "2") (pinfunction "2_2") (pintype "passive"))
      (node (ref "C6") (pin "2") (pinfunction "2_2") (pintype "passive"))
      (node (ref "C8") (pin "2") (pinfunction "2_2") (pintype "passive"))
      (node (ref "JP1") (pin "1") (pinfunction "1_1") (pintype "passive"))
      (node (ref "JP1") (pin "3") (pinfunction "3_3") (pintype "passive"))
      (node (ref "JP1") (pin "5") (pinfunction "5_5") (pintype "passive"))
      (node (ref "R131") (pin "1") (pinfunction "1_1") (pintype "passive"))
      (node (ref "R14") (pin "1") (pinfunction "1_1") (pintype "passive"))
      (node (ref "R17") (pin "2") (pinfunction "2_2") (pintype "passive"))
      (node (ref "R31") (pin "1") (pinfunction "1_1") (pintype "passive"))
      (node (ref "R34") (pin "2") (pinfunction "2_2") (pintype "passive"))
      (node (ref "R8") (pin "1") (pinfunction "1_1") (pintype "passive"))
      (node (ref "U1") (pin "3") (pinfunction "GND_3") (pintype "passive"))
      (node (ref "U10") (pin "4") (pinfunction "V-_4") (pintype "power_in"))
      (node (ref "U2") (pin "2") (pinfunction "GND_2") (pintype "passive"))
      (node (ref "U2") (pin "3") (pinfunction "GND_3") (pintype "passive"))
      (node (ref "U2") (pin "6") (pinfunction "GND_6") (pintype "passive"))
      (node (ref "U2") (pin "7") (pinfunction "GND_7") (pintype "passive"))
      (node (ref "U3") (pin "4") (pinfunction "V-_4") (pintype "power_in"))
      (node (ref "U4") (pin "4") (pinfunction "V-_4") (pintype "power_in"))
      (node (ref "U5") (pin "2") (pinfunction "IO_6_2") (pintype "bidirectional"))
      (node (ref "U5") (pin "4") (pinfunction "IO_7_4") (pintype "bidirectional"))
      (node (ref "U5") (pin "5") (pinfunction "IO_5_5") (pintype "bidirectional"))
      (node (ref "U5") (pin "6") (pinfunction "INH_6") (pintype "input"))
      (node (ref "U5") (pin "7") (pinfunction "GND_7") (pintype "power_in"))
      (node (ref "U5") (pin "8") (pinfunction "GND_8") (pintype "power_in"))
      (node (ref "U6") (pin "3") (pinfunction "IN-_3") (pintype "input"))
      (node (ref "U6") (pin "4") (pinfunction "GND_4") (pintype "power_in"))
      (node (ref "U8") (pin "4") (pinfunction "V-_4") (pintype "power_in"))
      (node (ref "U9") (pin "4") (pinfunction "V-_4") (pintype "power_in"))
    )
    (net (code "33") (name "DGND") (class "Default")
      (node (ref "C2") (pin "2") (pinfunction "2_2") (pintype "passive"))
      (node (ref "R131") (pin "2") (pinfunction "2_2") (pintype "passive"))
      (node (ref "U1") (pin "1") (pinfunction "GND_1") (pintype "passive"))
      (node (ref "U7") (pin "5") (pinfunction "GND_5") (pintype "passive"))
    )
    (net (code "34") (name "EARTH") (class "Default")
      (node (ref "C110") (pin "2") (pinfunction "2_2") (pintype "passive"))
      (node (ref "C111") (pin "2") (pinfunction "2_2") (pintype "passive"))
      (node (ref "C112") (pin "2") (pinfunction "2_2") (pintype "passive"))
      (node (ref "C113") (pin "2") (pinfunction "2_2") (pintype "passive"))
      (node (ref "C114") (pin "2") (pinfunction "2_2") (pintype "passive"))
      (node (ref "C115") (pin "2") (pinfunction "2_2") (pintype "passive"))
      (node (ref "C116") (pin "2") (pinfunction "2_2") (pintype "passive"))
      (node (ref "C117") (pin "2") (pinfunction "2_2") (pintype "passive"))
      (node (ref "C118") (pin "2") (pinfunction "2_2") (pintype "passive"))
      (node (ref "C119") (pin "2") (pinfunction "2_2") (pintype "passive"))
    )
    (net (code "35") (name "Net-(D1-A)") (class "Default")
      (node (ref "D1") (pin "4") (pinfunction "A_4") (pintype "passive"))
      (node (ref "U4") (pin "1") (pinfunction "OUT_1") (pintype "output"))
      (node (ref "U4") (pin "2") (pinfunction "IN-_2") (pintype "input"))
    )
    (net (code "36") (name "Net-(D1-K)") (class "Default")
      (node (ref "D1") (pin "8") (pinfunction "K_8") (pintype "passive"))
      (node (ref "R1") (pin "1") (pinfunction "1_1") (pintype "passive"))
      (node (ref "R4") (pin "2") (pinfunction "2_2") (pintype "passive"))
    )
    (net (code "37") (name "Net-(D2-A)") (class "Default")
      (node (ref "D2") (pin "4") (pinfunction "A_4") (pintype "passive"))
      (node (ref "U3") (pin "1") (pinfunction "OUT_1") (pintype "output"))
      (node (ref "U3") (pin "2") (pinfunction "IN-_2") (pintype "input"))
    )
    (net (code "38") (name "Net-(D2-K)") (class "Default")
      (node (ref "D2") (pin "8") (pinfunction "K_8") (pintype "passive"))
      (node (ref "R2") (pin "1") (pinfunction "1_1") (pintype "passive"))
      (node (ref "R5") (pin "2") (pinfunction "2_2") (pintype "passive"))
    )
    (net (code "39") (name "Net-(D3-A)") (class "Default")
      (node (ref "D3") (pin "4") (pinfunction "A_4") (pintype "passive"))
      (node (ref "U8") (pin "1") (pinfunction "OUT_1") (pintype "output"))
      (node (ref "U8") (pin "2") (pinfunction "IN-_2") (pintype "input"))
    )
    (net (code "40") (name "Net-(D3-K)") (class "Default")
      (node (ref "D3") (pin "8") (pinfunction "K_8") (pintype "passive"))
      (node (ref "R12") (pin "2") (pinfunction "2_2") (pintype "passive"))
      (node (ref "R9") (pin "1") (pinfunction "1_1") (pintype "passive"))
    )
    (net (code "41") (name "Net-(D4-A)") (class "Default")
      (node (ref "D4") (pin "4") (pinfunction "A_4") (pintype "passive"))
      (node (ref "U9") (pin "1") (pinfunction "OUT_1") (pintype "output"))
      (node (ref "U9") (pin "2") (pinfunction "IN-_2") (pintype "input"))
    )
    (net (code "42") (name "Net-(D4-K)") (class "Default")
      (node (ref "D4") (pin "8") (pinfunction "K_8") (pintype "passive"))
      (node (ref "R22") (pin "1") (pinfunction "1_1") (pintype "passive"))
      (node (ref "R29") (pin "2") (pinfunction "2_2") (pintype "passive"))
    )
    (net (code "43") (name "Net-(U3A-IN+)") (class "Default")
      (node (ref "C8") (pin "1") (pinfunction "1_1") (pintype "passive"))
      (node (ref "R5") (pin "1") (pinfunction "1_1") (pintype "passive"))
      (node (ref "R8") (pin "2") (pinfunction "2_2") (pintype "passive"))
      (node (ref "U3") (pin "3") (pinfunction "IN+_3") (pintype "input"))
      (node (ref "U3") (pin "5") (pinfunction "IN+_5") (pintype "input"))
    )
    (net (code "44") (name "Net-(U4B-IN+)") (class "Default")
      (node (ref "C10") (pin "1") (pinfunction "1_1") (pintype "passive"))
      (node (ref "R7") (pin "2") (pinfunction "2_2") (pintype "passive"))
      (node (ref "U4") (pin "5") (pinfunction "IN+_5") (pintype "input"))
    )
    (net (code "45") (name "Net-(U4B-IN-)") (class "Default")
      (node (ref "C7") (pin "1") (pinfunction "1_1") (pintype "passive"))
      (node (ref "R3") (pin "1") (pinfunction "1_1") (pintype "passive"))
      (node (ref "R6") (pin "2") (pinfunction "2_2") (pintype "passive"))
      (node (ref "U4") (pin "6") (pinfunction "IN-_6") (pintype "input"))
    )
    (net (code "46") (name "Net-(U5-IO_COM)") (class "Default")
      (node (ref "C12") (pin "1") (pinfunction "1_1") (pintype "passive"))
      (node (ref "U5") (pin "3") (pinfunction "IO_COM_3") (pintype "bidirectional"))
      (node (ref "U6") (pin "2") (pinfunction "IN+_2") (pintype "input"))
    )
    (net (code "47") (name "Net-(U8B-IN+)") (class "Default")
      (node (ref "C18") (pin "1") (pinfunction "1_1") (pintype "passive"))
      (node (ref "R15") (pin "2") (pinfunction "2_2") (pintype "passive"))
      (node (ref "U8") (pin "5") (pinfunction "IN+_5") (pintype "input"))
    )
    (net (code "48") (name "Net-(U8B-IN-)") (class "Default")
      (node (ref "C15") (pin "1") (pinfunction "1_1") (pintype "passive"))
      (node (ref "R10") (pin "1") (pinfunction "1_1") (pintype "passive"))
      (node (ref "R13") (pin "2") (pinfunction "2_2") (pintype "passive"))
      (node (ref "U8") (pin "6") (pinfunction "IN-_6") (pintype "input"))
    )
    (net (code "49") (name "Net-(U9B-IN+)") (class "Default")
      (node (ref "C26") (pin "1") (pinfunction "1_1") (pintype "passive"))
      (node (ref "R32") (pin "2") (pinfunction "2_2") (pintype "passive"))
      (node (ref "U9") (pin "5") (pinfunction "IN+_5") (pintype "input"))
    )
    (net (code "50") (name "Net-(U9B-IN-)") (class "Default")
      (node (ref "C23") (pin "1") (pinfunction "1_1") (pintype "passive"))
      (node (ref "R27") (pin "1") (pinfunction "1_1") (pintype "passive"))
      (node (ref "R30") (pin "2") (pinfunction "2_2") (pintype "passive"))
      (node (ref "U9") (pin "6") (pinfunction "IN-_6") (pintype "input"))
    )
    (net (code "51") (name "Net-(U10A-IN+)") (class "Default")
      (node (ref "C19") (pin "1") (pinfunction "1_1") (pintype "passive"))
      (node (ref "R16") (pin "2") (pinfunction "2_2") (pintype "passive"))
      (node (ref "U10") (pin "3") (pinfunction "IN+_3") (pintype "input"))
    )
    (net (code "52") (name "Net-(U10A-IN-)") (class "Default")
      (node (ref "C16") (pin "1") (pinfunction "1_1") (pintype "passive"))
      (node (ref "R11") (pin "1") (pinfunction "1_1") (pintype "passive"))
      (node (ref "R14") (pin "2") (pinfunction "2_2") (pintype "passive"))
      (node (ref "U10") (pin "2") (pinfunction "IN-_2") (pintype "input"))
    )
    (net (code "53") (name "Net-(U10B-IN+)") (class "Default")
      (node (ref "C27") (pin "1") (pinfunction "1_1") (pintype "passive"))
      (node (ref "R33") (pin "2") (pinfunction "2_2") (pintype "passive"))
      (node (ref "U10") (pin "5") (pinfunction "IN+_5") (pintype "input"))
    )
    (net (code "54") (name "Net-(U10B-IN-)") (class "Default")
      (node (ref "C24") (pin "1") (pinfunction "1_1") (pintype "passive"))
      (node (ref "R28") (pin "1") (pinfunction "1_1") (pintype "passive"))
      (node (ref "R31") (pin "2") (pinfunction "2_2") (pintype "passive"))
      (node (ref "U10") (pin "6") (pinfunction "IN-_6") (pintype "input"))
    )
    (net (code "55") (name "unconnected-(U2-NC-Pad4)") (class "Default")
      (node (ref "U2") (pin "4") (pinfunction "NC_4") (pintype "passive"))
    )
    (net (code "56") (name "unconnected-(U2-NC-Pad5)") (class "Default")
      (node (ref "U2") (pin "5") (pinfunction "NC_5") (pintype "passive"))
    )
    (net (code "57") (name "unconnected-(U7-DXN1-Pad2)") (class "Default")
      (node (ref "U7") (pin "2") (pinfunction "DXN1_2") (pintype "passive"))
    )
    (net (code "58") (name "unconnected-(U7-DXP1-Pad1)") (class "Default")
      (node (ref "U7") (pin "1") (pinfunction "DXP1_1") (pintype "passive"))
    )
  )
)
